# alu_schem_2.net
KiCad netlist of a schematic drawn in Altium Designer
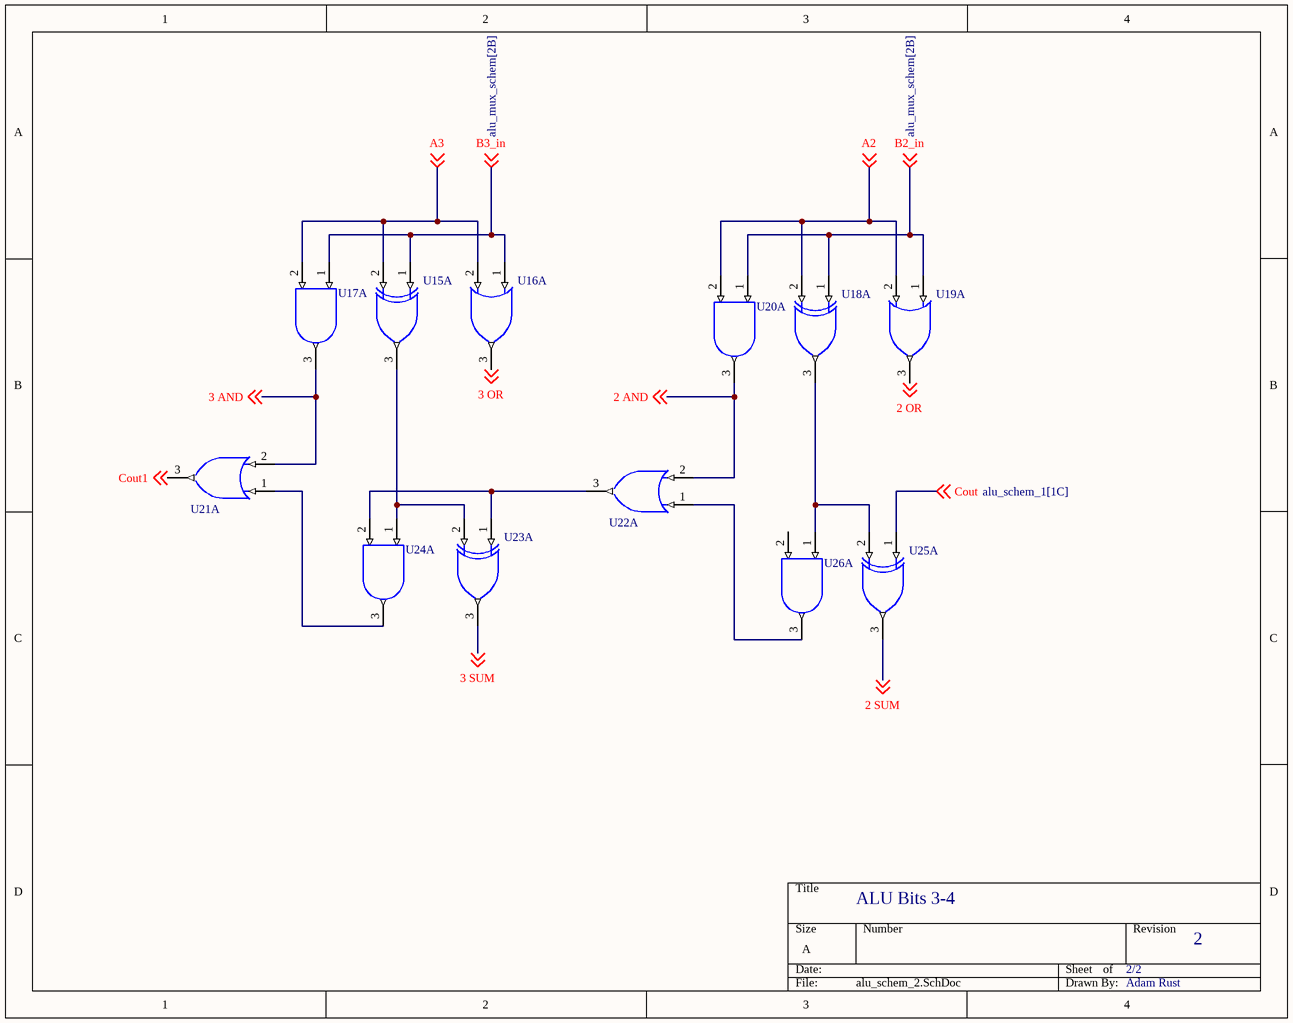
[diagram p0: alu_schem_2.SchDoc]

(export (version "E")
  (design (tool "Eeschema 10.0.6"))
  (components
    (comp (ref "U15")
      (value "SN74LVC86ARGYR")
      (footprint "RGY0014A_V")
      (description "Quadruple 2-Input Exclusive-OR Gate, RGY0014A, LARGE T&R")
      (fields
        (field (name "GENERIC PART NUMBER") "SN74LVC86A")
        (field (name "MANUFACTURER") "Texas Instruments")
      )
      (libsource (lib "Altium Content Vault") (part "TI-XOR-4-2IN-RGY0014A-14"))
    )
    (comp (ref "U16")
      (value "SN74LVC32APWRG4")
      (footprint "PW0014A_N")
      (description "Quadruple 2-Input Positive-OR Gate, PW0014A, LARGE T&R")
      (fields
        (field (name "GENERIC PART NUMBER") "SN74LVC32A")
        (field (name "MANUFACTURER") "Texas Instruments")
      )
      (libsource (lib "Altium Content Vault") (part "TI-OR-4-2IN-14"))
    )
    (comp (ref "U17")
      (value "SN74LVC08ADR")
      (footprint "D0014A_N")
      (description "Quadruple 2-Input Positive-AND Gate, D0014A, LARGE T&R")
      (fields
        (field (name "MANUFACTURER") "Texas Instruments")
        (field (name "GENERIC PART NUMBER") "SN74LVC08A")
      )
      (libsource (lib "Altium Content Vault") (part "TI-AND-4-2IN-14"))
    )
    (comp (ref "U18")
      (value "SN74LVC86ARGYR")
      (footprint "RGY0014A_V")
      (description "Quadruple 2-Input Exclusive-OR Gate, RGY0014A, LARGE T&R")
      (fields
        (field (name "GENERIC PART NUMBER") "SN74LVC86A")
        (field (name "MANUFACTURER") "Texas Instruments")
      )
      (libsource (lib "Altium Content Vault") (part "TI-XOR-4-2IN-RGY0014A-14"))
    )
    (comp (ref "U19")
      (value "SN74LVC32APWRG4")
      (footprint "PW0014A_N")
      (description "Quadruple 2-Input Positive-OR Gate, PW0014A, LARGE T&R")
      (fields
        (field (name "GENERIC PART NUMBER") "SN74LVC32A")
        (field (name "MANUFACTURER") "Texas Instruments")
      )
      (libsource (lib "Altium Content Vault") (part "TI-OR-4-2IN-14"))
    )
    (comp (ref "U20")
      (value "SN74LVC08ADR")
      (footprint "D0014A_N")
      (description "Quadruple 2-Input Positive-AND Gate, D0014A, LARGE T&R")
      (fields
        (field (name "MANUFACTURER") "Texas Instruments")
        (field (name "GENERIC PART NUMBER") "SN74LVC08A")
      )
      (libsource (lib "Altium Content Vault") (part "TI-AND-4-2IN-14"))
    )
    (comp (ref "U21")
      (value "SN74LVC32APWRG4")
      (footprint "PW0014A_N")
      (description "Quadruple 2-Input Positive-OR Gate, PW0014A, LARGE T&R")
      (fields
        (field (name "GENERIC PART NUMBER") "SN74LVC32A")
        (field (name "MANUFACTURER") "Texas Instruments")
      )
      (libsource (lib "") (part "TI-OR-4-2IN-14_1"))
    )
    (comp (ref "U22")
      (value "SN74LVC32APWRG4")
      (footprint "PW0014A_N")
      (description "Quadruple 2-Input Positive-OR Gate, PW0014A, LARGE T&R")
      (fields
        (field (name "GENERIC PART NUMBER") "SN74LVC32A")
        (field (name "MANUFACTURER") "Texas Instruments")
      )
      (libsource (lib "") (part "TI-OR-4-2IN-14_1"))
    )
    (comp (ref "U23")
      (value "SN74LVC86ARGYR")
      (footprint "RGY0014A_V")
      (description "Quadruple 2-Input Exclusive-OR Gate, RGY0014A, LARGE T&R")
      (fields
        (field (name "GENERIC PART NUMBER") "SN74LVC86A")
        (field (name "MANUFACTURER") "Texas Instruments")
      )
      (libsource (lib "Altium Content Vault") (part "TI-XOR-4-2IN-RGY0014A-14"))
    )
    (comp (ref "U24")
      (value "SN74LVC08ADR")
      (footprint "D0014A_N")
      (description "Quadruple 2-Input Positive-AND Gate, D0014A, LARGE T&R")
      (fields
        (field (name "MANUFACTURER") "Texas Instruments")
        (field (name "GENERIC PART NUMBER") "SN74LVC08A")
      )
      (libsource (lib "Altium Content Vault") (part "TI-AND-4-2IN-14"))
    )
    (comp (ref "U25")
      (value "SN74LVC86ARGYR")
      (footprint "RGY0014A_V")
      (description "Quadruple 2-Input Exclusive-OR Gate, RGY0014A, LARGE T&R")
      (fields
        (field (name "GENERIC PART NUMBER") "SN74LVC86A")
        (field (name "MANUFACTURER") "Texas Instruments")
      )
      (libsource (lib "Altium Content Vault") (part "TI-XOR-4-2IN-RGY0014A-14"))
    )
    (comp (ref "U26")
      (value "SN74LVC08ADR")
      (footprint "D0014A_N")
      (description "Quadruple 2-Input Positive-AND Gate, D0014A, LARGE T&R")
      (fields
        (field (name "MANUFACTURER") "Texas Instruments")
        (field (name "GENERIC PART NUMBER") "SN74LVC08A")
      )
      (libsource (lib "Altium Content Vault") (part "TI-AND-4-2IN-14"))
    )
  )
  (nets
    (net (code "1") (name "2 AND") (class "Default")
      (node (ref "U20") (pin "3") (pinfunction "1Y_3") (pintype "output"))
      (node (ref "U22") (pin "2") (pinfunction "1B_2") (pintype "input"))
    )
    (net (code "2") (name "2 OR") (class "Default")
      (node (ref "U19") (pin "3") (pinfunction "1Y_3") (pintype "output"))
    )
    (net (code "3") (name "2 SUM") (class "Default")
      (node (ref "U25") (pin "3") (pinfunction "1Y_3") (pintype "output"))
    )
    (net (code "4") (name "3 AND") (class "Default")
      (node (ref "U17") (pin "3") (pinfunction "1Y_3") (pintype "output"))
      (node (ref "U21") (pin "2") (pinfunction "1B_2") (pintype "input"))
    )
    (net (code "5") (name "3 OR") (class "Default")
      (node (ref "U16") (pin "3") (pinfunction "1Y_3") (pintype "output"))
    )
    (net (code "6") (name "3 SUM") (class "Default")
      (node (ref "U23") (pin "3") (pinfunction "1Y_3") (pintype "output"))
    )
    (net (code "7") (name "A2") (class "Default")
      (node (ref "U18") (pin "2") (pinfunction "1B_2") (pintype "input"))
      (node (ref "U19") (pin "2") (pinfunction "1B_2") (pintype "input"))
      (node (ref "U20") (pin "2") (pinfunction "1B_2") (pintype "input"))
    )
    (net (code "8") (name "A3") (class "Default")
      (node (ref "U15") (pin "2") (pinfunction "1B_2") (pintype "input"))
      (node (ref "U16") (pin "2") (pinfunction "1B_2") (pintype "input"))
      (node (ref "U17") (pin "2") (pinfunction "1B_2") (pintype "input"))
    )
    (net (code "9") (name "B2_in") (class "Default")
      (node (ref "U18") (pin "1") (pinfunction "1A_1") (pintype "input"))
      (node (ref "U19") (pin "1") (pinfunction "1A_1") (pintype "input"))
      (node (ref "U20") (pin "1") (pinfunction "1A_1") (pintype "input"))
    )
    (net (code "10") (name "B3_in") (class "Default")
      (node (ref "U15") (pin "1") (pinfunction "1A_1") (pintype "input"))
      (node (ref "U16") (pin "1") (pinfunction "1A_1") (pintype "input"))
      (node (ref "U17") (pin "1") (pinfunction "1A_1") (pintype "input"))
    )
    (net (code "11") (name "Cout") (class "Default")
      (node (ref "U25") (pin "1") (pinfunction "1A_1") (pintype "input"))
    )
    (net (code "12") (name "Cout1") (class "Default")
      (node (ref "U21") (pin "3") (pinfunction "1Y_3") (pintype "output"))
    )
    (net (code "13") (name "Net-(U15A-1Y)") (class "Default")
      (node (ref "U15") (pin "3") (pinfunction "1Y_3") (pintype "output"))
      (node (ref "U23") (pin "2") (pinfunction "1B_2") (pintype "input"))
      (node (ref "U24") (pin "1") (pinfunction "1A_1") (pintype "input"))
    )
    (net (code "14") (name "Net-(U18A-1Y)") (class "Default")
      (node (ref "U18") (pin "3") (pinfunction "1Y_3") (pintype "output"))
      (node (ref "U25") (pin "2") (pinfunction "1B_2") (pintype "input"))
      (node (ref "U26") (pin "1") (pinfunction "1A_1") (pintype "input"))
    )
    (net (code "15") (name "Net-(U21A-1A)") (class "Default")
      (node (ref "U21") (pin "1") (pinfunction "1A_1") (pintype "input"))
      (node (ref "U24") (pin "3") (pinfunction "1Y_3") (pintype "output"))
    )
    (net (code "16") (name "Net-(U22A-1A)") (class "Default")
      (node (ref "U22") (pin "1") (pinfunction "1A_1") (pintype "input"))
      (node (ref "U26") (pin "3") (pinfunction "1Y_3") (pintype "output"))
    )
    (net (code "17") (name "Net-(U22A-1Y)") (class "Default")
      (node (ref "U22") (pin "3") (pinfunction "1Y_3") (pintype "output"))
      (node (ref "U23") (pin "1") (pinfunction "1A_1") (pintype "input"))
      (node (ref "U24") (pin "2") (pinfunction "1B_2") (pintype "input"))
    )
    (net (code "18") (name "unconnected-(U26A-1B-Pad2)") (class "Default")
      (node (ref "U26") (pin "2") (pinfunction "1B_2") (pintype "input"))
    )
  )
)
